# PCB_REVISION2WORKING.net
KiCad netlist of a schematic drawn in EAGLE
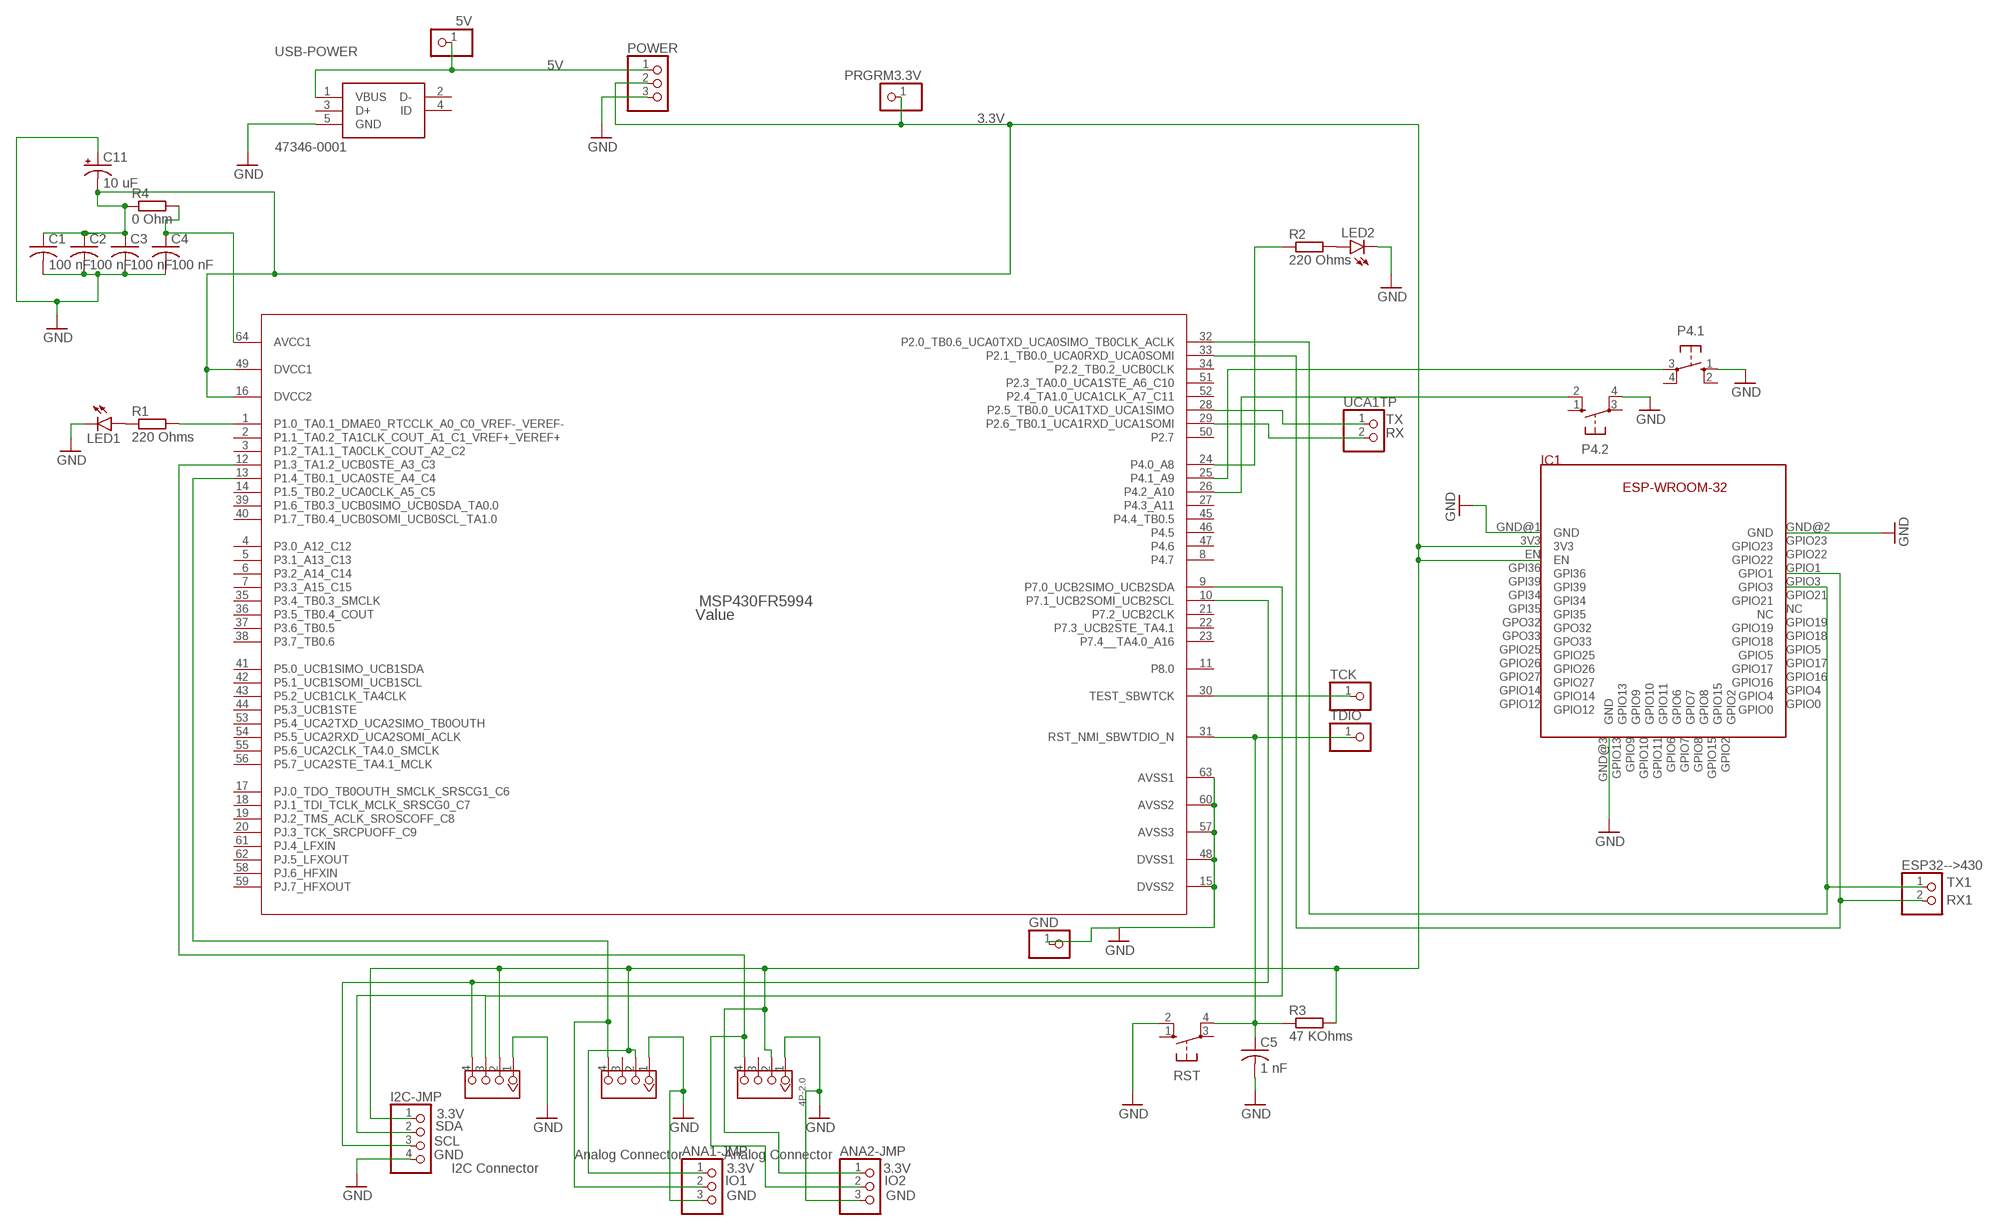
[diagram p0: schematic, sheet 1]

(export (version "E")
  (design (tool "Eeschema 10.0.6"))
  (components
    (comp (ref "5V")
      (value "PINHD-1X1")
      (footprint "eagle-import:1X01")
      (libsource (lib "eagle-import") (part "PINHD-1X1"))
    )
    (comp (ref "ANA1-JMP")
      (value "PINHD-1X3")
      (footprint "eagle-import:1X03")
      (libsource (lib "eagle-import") (part "PINHD-1X3"))
    )
    (comp (ref "ANA2-JMP")
      (value "PINHD-1X3")
      (footprint "eagle-import:1X03")
      (libsource (lib "eagle-import") (part "PINHD-1X3"))
    )
    (comp (ref "ANALOG1")
      (value "4P-2.0")
      (footprint "eagle-import:HW4-2.0")
      (libsource (lib "eagle-import") (part "GROVE-CONNECTOR-DIP(4P-2.0)"))
    )
    (comp (ref "ANALOG2")
      (value "4P-2.0")
      (footprint "eagle-import:HW4-2.0")
      (libsource (lib "eagle-import") (part "GROVE-CONNECTOR-DIP(4P-2.0)"))
    )
    (comp (ref "C1")
      (value "100 nF")
      (footprint "eagle-import:C0805K")
      (libsource (lib "eagle-import") (part "C-USC0805K"))
    )
    (comp (ref "C2")
      (value "100 nF")
      (footprint "eagle-import:C0805K")
      (libsource (lib "eagle-import") (part "C-USC0805K"))
    )
    (comp (ref "C3")
      (value "100 nF")
      (footprint "eagle-import:C0805K")
      (libsource (lib "eagle-import") (part "C-USC0805K"))
    )
    (comp (ref "C4")
      (value "100 nF")
      (footprint "eagle-import:C0805K")
      (libsource (lib "eagle-import") (part "C-USC0805K"))
    )
    (comp (ref "C5")
      (value "1 nF")
      (footprint "eagle-import:C0805K")
      (libsource (lib "eagle-import") (part "C-USC0805K"))
    )
    (comp (ref "C11")
      (value "10 uF")
      (footprint "eagle-import:E5-6")
      (libsource (lib "eagle-import") (part "CPOL-USE5-6"))
    )
    (comp (ref "ESP32-->430")
      (value "PINHD-1X2")
      (footprint "eagle-import:1X02")
      (libsource (lib "eagle-import") (part "PINHD-1X2"))
    )
    (comp (ref "GND")
      (value "PINHD-1X1")
      (footprint "eagle-import:1X01")
      (libsource (lib "eagle-import") (part "PINHD-1X1"))
    )
    (comp (ref "I2C")
      (value "4P-2.0")
      (footprint "eagle-import:HW4-2.0")
      (libsource (lib "eagle-import") (part "GROVE-CONNECTOR-DIP(4P-2.0)"))
    )
    (comp (ref "I2C-JMP")
      (value "PINHD-1X4")
      (footprint "eagle-import:1X04")
      (libsource (lib "eagle-import") (part "PINHD-1X4"))
    )
    (comp (ref "IC1")
      (value "ESPWROOM32")
      (footprint "eagle-import:ESPWROOM32")
      (libsource (lib "eagle-import") (part "ESPWROOM32"))
    )
    (comp (ref "LED1")
      (value "LED5MM")
      (footprint "eagle-import:LED5MM")
      (libsource (lib "eagle-import") (part "LED5MM"))
    )
    (comp (ref "LED2")
      (value "LED5MM")
      (footprint "eagle-import:LED5MM")
      (libsource (lib "eagle-import") (part "LED5MM"))
    )
    (comp (ref "MSP430FR5994")
      (value "Value")
      (footprint "eagle-import:PM0064A_N")
      (fields
        (field (name "MANUFACTURER") "Texas Instruments")
        (field (name "PARTNUMBER") "MSP430FR5964IPMR")
      )
      (libsource (lib "eagle-import") (part "MSP430FR5964IPMR"))
    )
    (comp (ref "P4.1")
      (value "10-XX")
      (footprint "eagle-import:B3F-10XX")
      (fields (field (name "MPN") "B3F-1000"))
      (libsource (lib "eagle-import") (part "10-XX"))
    )
    (comp (ref "P4.2")
      (value "10-XX")
      (footprint "eagle-import:B3F-10XX")
      (fields (field (name "MPN") "B3F-1000"))
      (libsource (lib "eagle-import") (part "10-XX"))
    )
    (comp (ref "POWER")
      (value "PINHD-1X3")
      (footprint "eagle-import:1X03")
      (libsource (lib "eagle-import") (part "PINHD-1X3"))
    )
    (comp (ref "PRGRM3.3V")
      (value "PINHD-1X1")
      (footprint "eagle-import:1X01")
      (libsource (lib "eagle-import") (part "PINHD-1X1"))
    )
    (comp (ref "R1")
      (value "220 Ohms")
      (footprint "eagle-import:M1206")
      (libsource (lib "eagle-import") (part "R-EU_M1206"))
    )
    (comp (ref "R2")
      (value "220 Ohms")
      (footprint "eagle-import:M1206")
      (libsource (lib "eagle-import") (part "R-EU_M1206"))
    )
    (comp (ref "R3")
      (value "47 KOhms")
      (footprint "eagle-import:M1206")
      (libsource (lib "eagle-import") (part "R-EU_M1206"))
    )
    (comp (ref "R4")
      (value "0 Ohm")
      (footprint "eagle-import:M1206")
      (libsource (lib "eagle-import") (part "R-EU_M1206"))
    )
    (comp (ref "RST")
      (value "10-XX")
      (footprint "eagle-import:B3F-10XX")
      (fields (field (name "MPN") "B3F-1000"))
      (libsource (lib "eagle-import") (part "10-XX"))
    )
    (comp (ref "TCK")
      (value "PINHD-1X1")
      (footprint "eagle-import:1X01")
      (libsource (lib "eagle-import") (part "PINHD-1X1"))
    )
    (comp (ref "TDIO")
      (value "PINHD-1X1")
      (footprint "eagle-import:1X01")
      (libsource (lib "eagle-import") (part "PINHD-1X1"))
    )
    (comp (ref "UCA1TP")
      (value "PINHD-1X2")
      (footprint "eagle-import:1X02")
      (libsource (lib "eagle-import") (part "PINHD-1X2"))
    )
    (comp (ref "USB-POWER")
      (value "47346-0001")
      (footprint "eagle-import:47346-0001")
      (fields (field (name "MOUSER_PART_NUMBER") "538-47346-0001"))
      (libsource (lib "eagle-import") (part "47346-0001"))
    )
  )
  (nets
    (net (code "1") (name "/3.3V") (class "Default")
      (node (ref "ANA1-JMP") (pin "1") (pinfunction "1_1") (pintype "passive"))
      (node (ref "ANA2-JMP") (pin "1") (pinfunction "1_1") (pintype "passive"))
      (node (ref "ANALOG1") (pin "2") (pinfunction "2_2") (pintype "bidirectional"))
      (node (ref "ANALOG2") (pin "2") (pinfunction "2_2") (pintype "bidirectional"))
      (node (ref "C1") (pin "1") (pinfunction "1_1") (pintype "passive"))
      (node (ref "C11") (pin "-") (pinfunction "-_-") (pintype "passive"))
      (node (ref "C2") (pin "1") (pinfunction "1_1") (pintype "passive"))
      (node (ref "C3") (pin "1") (pinfunction "1_1") (pintype "passive"))
      (node (ref "I2C") (pin "2") (pinfunction "2_2") (pintype "bidirectional"))
      (node (ref "I2C-JMP") (pin "1") (pinfunction "1_1") (pintype "passive"))
      (node (ref "IC1") (pin "3V3") (pinfunction "3V3_3V3") (pintype "bidirectional"))
      (node (ref "IC1") (pin "EN") (pinfunction "EN_EN") (pintype "bidirectional"))
      (node (ref "MSP430FR5994") (pin "16") (pinfunction "DVCC2_16") (pintype "power_in"))
      (node (ref "MSP430FR5994") (pin "49") (pinfunction "DVCC1_49") (pintype "power_in"))
      (node (ref "POWER") (pin "2") (pinfunction "2_2") (pintype "passive"))
      (node (ref "PRGRM3.3V") (pin "1") (pinfunction "1_1") (pintype "passive"))
      (node (ref "R3") (pin "2") (pinfunction "2_2") (pintype "passive"))
      (node (ref "R4") (pin "1") (pinfunction "1_1") (pintype "passive"))
    )
    (net (code "2") (name "/5V") (class "Default")
      (node (ref "5V") (pin "1") (pinfunction "1_1") (pintype "passive"))
      (node (ref "POWER") (pin "1") (pinfunction "1_1") (pintype "passive"))
      (node (ref "USB-POWER") (pin "1") (pinfunction "VBUS_1") (pintype "bidirectional"))
    )
    (net (code "3") (name "/IO1") (class "Default")
      (node (ref "ANA1-JMP") (pin "2") (pinfunction "2_2") (pintype "passive"))
      (node (ref "ANALOG1") (pin "4") (pinfunction "4_4") (pintype "bidirectional"))
      (node (ref "MSP430FR5994") (pin "13") (pinfunction "P1.4_TB0.1_UCA0STE_A4_C4_13") (pintype "bidirectional"))
    )
    (net (code "4") (name "/IO2") (class "Default")
      (node (ref "ANA2-JMP") (pin "2") (pinfunction "2_2") (pintype "passive"))
      (node (ref "ANALOG2") (pin "4") (pinfunction "4_4") (pintype "bidirectional"))
      (node (ref "MSP430FR5994") (pin "12") (pinfunction "P1.3_TA1.2_UCB0STE_A3_C3_12") (pintype "bidirectional"))
    )
    (net (code "5") (name "/RX") (class "Default")
      (node (ref "MSP430FR5994") (pin "29") (pinfunction "P2.6_TB0.1_UCA1RXD_UCA1SOMI_29") (pintype "bidirectional"))
      (node (ref "UCA1TP") (pin "2") (pinfunction "2_2") (pintype "passive"))
    )
    (net (code "6") (name "/RX1") (class "Default")
      (node (ref "ESP32-->430") (pin "2") (pinfunction "2_2") (pintype "passive"))
      (node (ref "IC1") (pin "GPIO1") (pinfunction "GPIO1_GPIO1") (pintype "bidirectional"))
      (node (ref "MSP430FR5994") (pin "33") (pinfunction "P2.1_TB0.0_UCA0RXD_UCA0SOMI_33") (pintype "bidirectional"))
    )
    (net (code "7") (name "/SCL") (class "Default")
      (node (ref "I2C") (pin "4") (pinfunction "4_4") (pintype "bidirectional"))
      (node (ref "I2C-JMP") (pin "3") (pinfunction "3_3") (pintype "passive"))
      (node (ref "MSP430FR5994") (pin "10") (pinfunction "P7.1_UCB2SOMI_UCB2SCL_10") (pintype "bidirectional"))
    )
    (net (code "8") (name "/SDA") (class "Default")
      (node (ref "I2C") (pin "3") (pinfunction "3_3") (pintype "bidirectional"))
      (node (ref "I2C-JMP") (pin "2") (pinfunction "2_2") (pintype "passive"))
      (node (ref "MSP430FR5994") (pin "9") (pinfunction "P7.0_UCB2SIMO_UCB2SDA_9") (pintype "bidirectional"))
    )
    (net (code "9") (name "/TX") (class "Default")
      (node (ref "MSP430FR5994") (pin "28") (pinfunction "P2.5_TB0.0_UCA1TXD_UCA1SIMO_28") (pintype "bidirectional"))
      (node (ref "UCA1TP") (pin "1") (pinfunction "1_1") (pintype "passive"))
    )
    (net (code "10") (name "/TX1") (class "Default")
      (node (ref "ESP32-->430") (pin "1") (pinfunction "1_1") (pintype "passive"))
      (node (ref "IC1") (pin "GPIO3") (pinfunction "GPIO3_GPIO3") (pintype "bidirectional"))
      (node (ref "MSP430FR5994") (pin "32") (pinfunction "P2.0_TB0.6_UCA0TXD_UCA0SIMO_TB0CLK_ACLK_32") (pintype "bidirectional"))
    )
    (net (code "11") (name "GND") (class "Default")
      (node (ref "ANA1-JMP") (pin "3") (pinfunction "3_3") (pintype "passive"))
      (node (ref "ANA2-JMP") (pin "3") (pinfunction "3_3") (pintype "passive"))
      (node (ref "ANALOG1") (pin "1") (pinfunction "1_1") (pintype "bidirectional"))
      (node (ref "ANALOG2") (pin "1") (pinfunction "1_1") (pintype "bidirectional"))
      (node (ref "C1") (pin "2") (pinfunction "2_2") (pintype "passive"))
      (node (ref "C11") (pin "+") (pinfunction "+_+") (pintype "passive"))
      (node (ref "C2") (pin "2") (pinfunction "2_2") (pintype "passive"))
      (node (ref "C3") (pin "2") (pinfunction "2_2") (pintype "passive"))
      (node (ref "C4") (pin "2") (pinfunction "2_2") (pintype "passive"))
      (node (ref "C5") (pin "2") (pinfunction "2_2") (pintype "passive"))
      (node (ref "GND") (pin "1") (pinfunction "1_1") (pintype "passive"))
      (node (ref "I2C") (pin "1") (pinfunction "1_1") (pintype "bidirectional"))
      (node (ref "I2C-JMP") (pin "4") (pinfunction "4_4") (pintype "passive"))
      (node (ref "IC1") (pin "GND@1") (pinfunction "GND_GND@1") (pintype "bidirectional"))
      (node (ref "IC1") (pin "GND@2") (pinfunction "GND_GND@2") (pintype "bidirectional"))
      (node (ref "IC1") (pin "GND@3") (pinfunction "GND_GND@3") (pintype "bidirectional"))
      (node (ref "LED1") (pin "K") (pinfunction "C_K") (pintype "passive"))
      (node (ref "LED2") (pin "K") (pinfunction "C_K") (pintype "passive"))
      (node (ref "MSP430FR5994") (pin "15") (pinfunction "DVSS2_15") (pintype "power_in"))
      (node (ref "MSP430FR5994") (pin "48") (pinfunction "DVSS1_48") (pintype "power_in"))
      (node (ref "MSP430FR5994") (pin "57") (pinfunction "AVSS3_57") (pintype "power_in"))
      (node (ref "MSP430FR5994") (pin "60") (pinfunction "AVSS2_60") (pintype "power_in"))
      (node (ref "MSP430FR5994") (pin "63") (pinfunction "AVSS1_63") (pintype "power_in"))
      (node (ref "P4.1") (pin "1") (pinfunction "S_1") (pintype "passive"))
      (node (ref "P4.2") (pin "4") (pinfunction "P1_4") (pintype "passive"))
      (node (ref "POWER") (pin "3") (pinfunction "3_3") (pintype "passive"))
      (node (ref "RST") (pin "2") (pinfunction "S1_2") (pintype "passive"))
      (node (ref "USB-POWER") (pin "5") (pinfunction "GND_5") (pintype "bidirectional"))
    )
    (net (code "12") (name "Net-(LED1-PadA)") (class "Default")
      (node (ref "LED1") (pin "A") (pinfunction "A_A") (pintype "passive"))
      (node (ref "R1") (pin "1") (pinfunction "1_1") (pintype "passive"))
    )
    (net (code "13") (name "Net-(LED2-PadA)") (class "Default")
      (node (ref "LED2") (pin "A") (pinfunction "A_A") (pintype "passive"))
      (node (ref "R2") (pin "2") (pinfunction "2_2") (pintype "passive"))
    )
    (net (code "14") (name "Net-(MSP430FR5994-AVCC1)") (class "Default")
      (node (ref "C4") (pin "1") (pinfunction "1_1") (pintype "passive"))
      (node (ref "MSP430FR5994") (pin "64") (pinfunction "AVCC1_64") (pintype "power_in"))
      (node (ref "R4") (pin "2") (pinfunction "2_2") (pintype "passive"))
    )
    (net (code "15") (name "Net-(MSP430FR5994-P1.0_TA0.1_DMAE0_RTCCLK_A0_C0_VREF-_VEREF-)") (class "Default")
      (node (ref "MSP430FR5994") (pin "1") (pinfunction "P1.0_TA0.1_DMAE0_RTCCLK_A0_C0_VREF-_VEREF-_1") (pintype "bidirectional"))
      (node (ref "R1") (pin "2") (pinfunction "2_2") (pintype "passive"))
    )
    (net (code "16") (name "Net-(MSP430FR5994-P4.0_A8)") (class "Default")
      (node (ref "MSP430FR5994") (pin "24") (pinfunction "P4.0_A8_24") (pintype "bidirectional"))
      (node (ref "R2") (pin "1") (pinfunction "1_1") (pintype "passive"))
    )
    (net (code "17") (name "Net-(MSP430FR5994-P4.1_A9)") (class "Default")
      (node (ref "MSP430FR5994") (pin "25") (pinfunction "P4.1_A9_25") (pintype "bidirectional"))
      (node (ref "P4.1") (pin "3") (pinfunction "P_3") (pintype "passive"))
    )
    (net (code "18") (name "Net-(MSP430FR5994-P4.2_A10)") (class "Default")
      (node (ref "MSP430FR5994") (pin "26") (pinfunction "P4.2_A10_26") (pintype "bidirectional"))
      (node (ref "P4.2") (pin "2") (pinfunction "S1_2") (pintype "passive"))
    )
    (net (code "19") (name "Net-(MSP430FR5994-RST_NMI_SBWTDIO_N)") (class "Default")
      (node (ref "C5") (pin "1") (pinfunction "1_1") (pintype "passive"))
      (node (ref "MSP430FR5994") (pin "31") (pinfunction "RST_NMI_SBWTDIO_N_31") (pintype "bidirectional"))
      (node (ref "R3") (pin "1") (pinfunction "1_1") (pintype "passive"))
      (node (ref "RST") (pin "4") (pinfunction "P1_4") (pintype "passive"))
      (node (ref "TDIO") (pin "1") (pinfunction "1_1") (pintype "passive"))
    )
    (net (code "20") (name "Net-(MSP430FR5994-TEST_SBWTCK)") (class "Default")
      (node (ref "MSP430FR5994") (pin "30") (pinfunction "TEST_SBWTCK_30") (pintype "input"))
      (node (ref "TCK") (pin "1") (pinfunction "1_1") (pintype "passive"))
    )
    (net (code "21") (name "unconnected-(ANALOG1-Pad3)") (class "Default")
      (node (ref "ANALOG1") (pin "3") (pinfunction "3_3") (pintype "bidirectional"))
    )
    (net (code "22") (name "unconnected-(ANALOG2-Pad3)") (class "Default")
      (node (ref "ANALOG2") (pin "3") (pinfunction "3_3") (pintype "bidirectional"))
    )
    (net (code "23") (name "unconnected-(IC1-PadGPI34)") (class "Default")
      (node (ref "IC1") (pin "GPI34") (pinfunction "GPI34_GPI34") (pintype "bidirectional"))
    )
    (net (code "24") (name "unconnected-(IC1-PadGPI35)") (class "Default")
      (node (ref "IC1") (pin "GPI35") (pinfunction "GPI35_GPI35") (pintype "bidirectional"))
    )
    (net (code "25") (name "unconnected-(IC1-PadGPI36)") (class "Default")
      (node (ref "IC1") (pin "GPI36") (pinfunction "GPI36_GPI36") (pintype "bidirectional"))
    )
    (net (code "26") (name "unconnected-(IC1-PadGPI39)") (class "Default")
      (node (ref "IC1") (pin "GPI39") (pinfunction "GPI39_GPI39") (pintype "bidirectional"))
    )
    (net (code "27") (name "unconnected-(IC1-PadGPIO0)") (class "Default")
      (node (ref "IC1") (pin "GPIO0") (pinfunction "GPIO0_GPIO0") (pintype "bidirectional"))
    )
    (net (code "28") (name "unconnected-(IC1-PadGPIO2)") (class "Default")
      (node (ref "IC1") (pin "GPIO2") (pinfunction "GPIO2_GPIO2") (pintype "bidirectional"))
    )
    (net (code "29") (name "unconnected-(IC1-PadGPIO4)") (class "Default")
      (node (ref "IC1") (pin "GPIO4") (pinfunction "GPIO4_GPIO4") (pintype "bidirectional"))
    )
    (net (code "30") (name "unconnected-(IC1-PadGPIO5)") (class "Default")
      (node (ref "IC1") (pin "GPIO5") (pinfunction "GPIO5_GPIO5") (pintype "bidirectional"))
    )
    (net (code "31") (name "unconnected-(IC1-PadGPIO6)") (class "Default")
      (node (ref "IC1") (pin "GPIO6") (pinfunction "GPIO6_GPIO6") (pintype "bidirectional"))
    )
    (net (code "32") (name "unconnected-(IC1-PadGPIO7)") (class "Default")
      (node (ref "IC1") (pin "GPIO7") (pinfunction "GPIO7_GPIO7") (pintype "bidirectional"))
    )
    (net (code "33") (name "unconnected-(IC1-PadGPIO8)") (class "Default")
      (node (ref "IC1") (pin "GPIO8") (pinfunction "GPIO8_GPIO8") (pintype "bidirectional"))
    )
    (net (code "34") (name "unconnected-(IC1-PadGPIO9)") (class "Default")
      (node (ref "IC1") (pin "GPIO9") (pinfunction "GPIO9_GPIO9") (pintype "bidirectional"))
    )
    (net (code "35") (name "unconnected-(IC1-PadGPIO10)") (class "Default")
      (node (ref "IC1") (pin "GPIO10") (pinfunction "GPIO10_GPIO10") (pintype "bidirectional"))
    )
    (net (code "36") (name "unconnected-(IC1-PadGPIO11)") (class "Default")
      (node (ref "IC1") (pin "GPIO11") (pinfunction "GPIO11_GPIO11") (pintype "bidirectional"))
    )
    (net (code "37") (name "unconnected-(IC1-PadGPIO12)") (class "Default")
      (node (ref "IC1") (pin "GPIO12") (pinfunction "GPIO12_GPIO12") (pintype "bidirectional"))
    )
    (net (code "38") (name "unconnected-(IC1-PadGPIO13)") (class "Default")
      (node (ref "IC1") (pin "GPIO13") (pinfunction "GPIO13_GPIO13") (pintype "bidirectional"))
    )
    (net (code "39") (name "unconnected-(IC1-PadGPIO14)") (class "Default")
      (node (ref "IC1") (pin "GPIO14") (pinfunction "GPIO14_GPIO14") (pintype "bidirectional"))
    )
    (net (code "40") (name "unconnected-(IC1-PadGPIO15)") (class "Default")
      (node (ref "IC1") (pin "GPIO15") (pinfunction "GPIO15_GPIO15") (pintype "bidirectional"))
    )
    (net (code "41") (name "unconnected-(IC1-PadGPIO16)") (class "Default")
      (node (ref "IC1") (pin "GPIO16") (pinfunction "GPIO16_GPIO16") (pintype "bidirectional"))
    )
    (net (code "42") (name "unconnected-(IC1-PadGPIO17)") (class "Default")
      (node (ref "IC1") (pin "GPIO17") (pinfunction "GPIO17_GPIO17") (pintype "bidirectional"))
    )
    (net (code "43") (name "unconnected-(IC1-PadGPIO18)") (class "Default")
      (node (ref "IC1") (pin "GPIO18") (pinfunction "GPIO18_GPIO18") (pintype "bidirectional"))
    )
    (net (code "44") (name "unconnected-(IC1-PadGPIO19)") (class "Default")
      (node (ref "IC1") (pin "GPIO19") (pinfunction "GPIO19_GPIO19") (pintype "bidirectional"))
    )
    (net (code "45") (name "unconnected-(IC1-PadGPIO21)") (class "Default")
      (node (ref "IC1") (pin "GPIO21") (pinfunction "GPIO21_GPIO21") (pintype "bidirectional"))
    )
    (net (code "46") (name "unconnected-(IC1-PadGPIO22)") (class "Default")
      (node (ref "IC1") (pin "GPIO22") (pinfunction "GPIO22_GPIO22") (pintype "bidirectional"))
    )
    (net (code "47") (name "unconnected-(IC1-PadGPIO23)") (class "Default")
      (node (ref "IC1") (pin "GPIO23") (pinfunction "GPIO23_GPIO23") (pintype "bidirectional"))
    )
    (net (code "48") (name "unconnected-(IC1-PadGPIO25)") (class "Default")
      (node (ref "IC1") (pin "GPIO25") (pinfunction "GPIO25_GPIO25") (pintype "bidirectional"))
    )
    (net (code "49") (name "unconnected-(IC1-PadGPIO26)") (class "Default")
      (node (ref "IC1") (pin "GPIO26") (pinfunction "GPIO26_GPIO26") (pintype "bidirectional"))
    )
    (net (code "50") (name "unconnected-(IC1-PadGPIO27)") (class "Default")
      (node (ref "IC1") (pin "GPIO27") (pinfunction "GPIO27_GPIO27") (pintype "bidirectional"))
    )
    (net (code "51") (name "unconnected-(IC1-PadGPO32)") (class "Default")
      (node (ref "IC1") (pin "GPO32") (pinfunction "GPO32_GPO32") (pintype "bidirectional"))
    )
    (net (code "52") (name "unconnected-(IC1-PadGPO33)") (class "Default")
      (node (ref "IC1") (pin "GPO33") (pinfunction "GPO33_GPO33") (pintype "bidirectional"))
    )
    (net (code "53") (name "unconnected-(IC1-PadNC)") (class "Default")
      (node (ref "IC1") (pin "NC") (pinfunction "NC_NC") (pintype "bidirectional"))
    )
    (net (code "54") (name "unconnected-(MSP430FR5994-P1.1_TA0.2_TA1CLK_COUT_A1_C1_VREF+_VEREF+-Pad2)") (class "Default")
      (node (ref "MSP430FR5994") (pin "2") (pinfunction "P1.1_TA0.2_TA1CLK_COUT_A1_C1_VREF+_VEREF+_2") (pintype "bidirectional"))
    )
    (net (code "55") (name "unconnected-(MSP430FR5994-P1.2_TA1.1_TA0CLK_COUT_A2_C2-Pad3)") (class "Default")
      (node (ref "MSP430FR5994") (pin "3") (pinfunction "P1.2_TA1.1_TA0CLK_COUT_A2_C2_3") (pintype "bidirectional"))
    )
    (net (code "56") (name "unconnected-(MSP430FR5994-P1.5_TB0.2_UCA0CLK_A5_C5-Pad14)") (class "Default")
      (node (ref "MSP430FR5994") (pin "14") (pinfunction "P1.5_TB0.2_UCA0CLK_A5_C5_14") (pintype "bidirectional"))
    )
    (net (code "57") (name "unconnected-(MSP430FR5994-P1.6_TB0.3_UCB0SIMO_UCB0SDA_TA0.0-Pad39)") (class "Default")
      (node (ref "MSP430FR5994") (pin "39") (pinfunction "P1.6_TB0.3_UCB0SIMO_UCB0SDA_TA0.0_39") (pintype "bidirectional"))
    )
    (net (code "58") (name "unconnected-(MSP430FR5994-P1.7_TB0.4_UCB0SOMI_UCB0SCL_TA1.0-Pad40)") (class "Default")
      (node (ref "MSP430FR5994") (pin "40") (pinfunction "P1.7_TB0.4_UCB0SOMI_UCB0SCL_TA1.0_40") (pintype "bidirectional"))
    )
    (net (code "59") (name "unconnected-(MSP430FR5994-P2.2_TB0.2_UCB0CLK-Pad34)") (class "Default")
      (node (ref "MSP430FR5994") (pin "34") (pinfunction "P2.2_TB0.2_UCB0CLK_34") (pintype "bidirectional"))
    )
    (net (code "60") (name "unconnected-(MSP430FR5994-P2.3_TA0.0_UCA1STE_A6_C10-Pad51)") (class "Default")
      (node (ref "MSP430FR5994") (pin "51") (pinfunction "P2.3_TA0.0_UCA1STE_A6_C10_51") (pintype "bidirectional"))
    )
    (net (code "61") (name "unconnected-(MSP430FR5994-P2.4_TA1.0_UCA1CLK_A7_C11-Pad52)") (class "Default")
      (node (ref "MSP430FR5994") (pin "52") (pinfunction "P2.4_TA1.0_UCA1CLK_A7_C11_52") (pintype "bidirectional"))
    )
    (net (code "62") (name "unconnected-(MSP430FR5994-P2.7-Pad50)") (class "Default")
      (node (ref "MSP430FR5994") (pin "50") (pinfunction "P2.7_50") (pintype "bidirectional"))
    )
    (net (code "63") (name "unconnected-(MSP430FR5994-P3.0_A12_C12-Pad4)") (class "Default")
      (node (ref "MSP430FR5994") (pin "4") (pinfunction "P3.0_A12_C12_4") (pintype "bidirectional"))
    )
    (net (code "64") (name "unconnected-(MSP430FR5994-P3.1_A13_C13-Pad5)") (class "Default")
      (node (ref "MSP430FR5994") (pin "5") (pinfunction "P3.1_A13_C13_5") (pintype "bidirectional"))
    )
    (net (code "65") (name "unconnected-(MSP430FR5994-P3.2_A14_C14-Pad6)") (class "Default")
      (node (ref "MSP430FR5994") (pin "6") (pinfunction "P3.2_A14_C14_6") (pintype "bidirectional"))
    )
    (net (code "66") (name "unconnected-(MSP430FR5994-P3.3_A15_C15-Pad7)") (class "Default")
      (node (ref "MSP430FR5994") (pin "7") (pinfunction "P3.3_A15_C15_7") (pintype "bidirectional"))
    )
    (net (code "67") (name "unconnected-(MSP430FR5994-P3.4_TB0.3_SMCLK-Pad35)") (class "Default")
      (node (ref "MSP430FR5994") (pin "35") (pinfunction "P3.4_TB0.3_SMCLK_35") (pintype "bidirectional"))
    )
    (net (code "68") (name "unconnected-(MSP430FR5994-P3.5_TB0.4_COUT-Pad36)") (class "Default")
      (node (ref "MSP430FR5994") (pin "36") (pinfunction "P3.5_TB0.4_COUT_36") (pintype "bidirectional"))
    )
    (net (code "69") (name "unconnected-(MSP430FR5994-P3.6_TB0.5-Pad37)") (class "Default")
      (node (ref "MSP430FR5994") (pin "37") (pinfunction "P3.6_TB0.5_37") (pintype "bidirectional"))
    )
    (net (code "70") (name "unconnected-(MSP430FR5994-P3.7_TB0.6-Pad38)") (class "Default")
      (node (ref "MSP430FR5994") (pin "38") (pinfunction "P3.7_TB0.6_38") (pintype "bidirectional"))
    )
    (net (code "71") (name "unconnected-(MSP430FR5994-P4.3_A11-Pad27)") (class "Default")
      (node (ref "MSP430FR5994") (pin "27") (pinfunction "P4.3_A11_27") (pintype "bidirectional"))
    )
    (net (code "72") (name "unconnected-(MSP430FR5994-P4.4_TB0.5-Pad45)") (class "Default")
      (node (ref "MSP430FR5994") (pin "45") (pinfunction "P4.4_TB0.5_45") (pintype "bidirectional"))
    )
    (net (code "73") (name "unconnected-(MSP430FR5994-P4.5-Pad46)") (class "Default")
      (node (ref "MSP430FR5994") (pin "46") (pinfunction "P4.5_46") (pintype "bidirectional"))
    )
    (net (code "74") (name "unconnected-(MSP430FR5994-P4.6-Pad47)") (class "Default")
      (node (ref "MSP430FR5994") (pin "47") (pinfunction "P4.6_47") (pintype "bidirectional"))
    )
    (net (code "75") (name "unconnected-(MSP430FR5994-P4.7-Pad8)") (class "Default")
      (node (ref "MSP430FR5994") (pin "8") (pinfunction "P4.7_8") (pintype "bidirectional"))
    )
    (net (code "76") (name "unconnected-(MSP430FR5994-P5.0_UCB1SIMO_UCB1SDA-Pad41)") (class "Default")
      (node (ref "MSP430FR5994") (pin "41") (pinfunction "P5.0_UCB1SIMO_UCB1SDA_41") (pintype "bidirectional"))
    )
    (net (code "77") (name "unconnected-(MSP430FR5994-P5.1_UCB1SOMI_UCB1SCL-Pad42)") (class "Default")
      (node (ref "MSP430FR5994") (pin "42") (pinfunction "P5.1_UCB1SOMI_UCB1SCL_42") (pintype "bidirectional"))
    )
    (net (code "78") (name "unconnected-(MSP430FR5994-P5.2_UCB1CLK_TA4CLK-Pad43)") (class "Default")
      (node (ref "MSP430FR5994") (pin "43") (pinfunction "P5.2_UCB1CLK_TA4CLK_43") (pintype "bidirectional"))
    )
    (net (code "79") (name "unconnected-(MSP430FR5994-P5.3_UCB1STE-Pad44)") (class "Default")
      (node (ref "MSP430FR5994") (pin "44") (pinfunction "P5.3_UCB1STE_44") (pintype "bidirectional"))
    )
    (net (code "80") (name "unconnected-(MSP430FR5994-P5.4_UCA2TXD_UCA2SIMO_TB0OUTH-Pad53)") (class "Default")
      (node (ref "MSP430FR5994") (pin "53") (pinfunction "P5.4_UCA2TXD_UCA2SIMO_TB0OUTH_53") (pintype "bidirectional"))
    )
    (net (code "81") (name "unconnected-(MSP430FR5994-P5.5_UCA2RXD_UCA2SOMI_ACLK-Pad54)") (class "Default")
      (node (ref "MSP430FR5994") (pin "54") (pinfunction "P5.5_UCA2RXD_UCA2SOMI_ACLK_54") (pintype "bidirectional"))
    )
    (net (code "82") (name "unconnected-(MSP430FR5994-P5.6_UCA2CLK_TA4.0_SMCLK-Pad55)") (class "Default")
      (node (ref "MSP430FR5994") (pin "55") (pinfunction "P5.6_UCA2CLK_TA4.0_SMCLK_55") (pintype "bidirectional"))
    )
    (net (code "83") (name "unconnected-(MSP430FR5994-P5.7_UCA2STE_TA4.1_MCLK-Pad56)") (class "Default")
      (node (ref "MSP430FR5994") (pin "56") (pinfunction "P5.7_UCA2STE_TA4.1_MCLK_56") (pintype "bidirectional"))
    )
    (net (code "84") (name "unconnected-(MSP430FR5994-P7.2_UCB2CLK-Pad21)") (class "Default")
      (node (ref "MSP430FR5994") (pin "21") (pinfunction "P7.2_UCB2CLK_21") (pintype "bidirectional"))
    )
    (net (code "85") (name "unconnected-(MSP430FR5994-P7.3_UCB2STE_TA4.1-Pad22)") (class "Default")
      (node (ref "MSP430FR5994") (pin "22") (pinfunction "P7.3_UCB2STE_TA4.1_22") (pintype "bidirectional"))
    )
    (net (code "86") (name "unconnected-(MSP430FR5994-P7.4__TA4.0_A16-Pad23)") (class "Default")
      (node (ref "MSP430FR5994") (pin "23") (pinfunction "P7.4__TA4.0_A16_23") (pintype "bidirectional"))
    )
    (net (code "87") (name "unconnected-(MSP430FR5994-P8.0-Pad11)") (class "Default")
      (node (ref "MSP430FR5994") (pin "11") (pinfunction "P8.0_11") (pintype "bidirectional"))
    )
    (net (code "88") (name "unconnected-(MSP430FR5994-PJ.0_TDO_TB0OUTH_SMCLK_SRSCG1_C6-Pad17)") (class "Default")
      (node (ref "MSP430FR5994") (pin "17") (pinfunction "PJ.0_TDO_TB0OUTH_SMCLK_SRSCG1_C6_17") (pintype "bidirectional"))
    )
    (net (code "89") (name "unconnected-(MSP430FR5994-PJ.1_TDI_TCLK_MCLK_SRSCG0_C7-Pad18)") (class "Default")
      (node (ref "MSP430FR5994") (pin "18") (pinfunction "PJ.1_TDI_TCLK_MCLK_SRSCG0_C7_18") (pintype "bidirectional"))
    )
    (net (code "90") (name "unconnected-(MSP430FR5994-PJ.2_TMS_ACLK_SROSCOFF_C8-Pad19)") (class "Default")
      (node (ref "MSP430FR5994") (pin "19") (pinfunction "PJ.2_TMS_ACLK_SROSCOFF_C8_19") (pintype "bidirectional"))
    )
    (net (code "91") (name "unconnected-(MSP430FR5994-PJ.3_TCK_SRCPUOFF_C9-Pad20)") (class "Default")
      (node (ref "MSP430FR5994") (pin "20") (pinfunction "PJ.3_TCK_SRCPUOFF_C9_20") (pintype "bidirectional"))
    )
    (net (code "92") (name "unconnected-(MSP430FR5994-PJ.4_LFXIN-Pad61)") (class "Default")
      (node (ref "MSP430FR5994") (pin "61") (pinfunction "PJ.4_LFXIN_61") (pintype "bidirectional"))
    )
    (net (code "93") (name "unconnected-(MSP430FR5994-PJ.5_LFXOUT-Pad62)") (class "Default")
      (node (ref "MSP430FR5994") (pin "62") (pinfunction "PJ.5_LFXOUT_62") (pintype "bidirectional"))
    )
    (net (code "94") (name "unconnected-(MSP430FR5994-PJ.6_HFXIN-Pad58)") (class "Default")
      (node (ref "MSP430FR5994") (pin "58") (pinfunction "PJ.6_HFXIN_58") (pintype "bidirectional"))
    )
    (net (code "95") (name "unconnected-(MSP430FR5994-PJ.7_HFXOUT-Pad59)") (class "Default")
      (node (ref "MSP430FR5994") (pin "59") (pinfunction "PJ.7_HFXOUT_59") (pintype "bidirectional"))
    )
    (net (code "96") (name "unconnected-(P4.1-P1-Pad4)") (class "Default")
      (node (ref "P4.1") (pin "4") (pinfunction "P1_4") (pintype "passive"))
    )
    (net (code "97") (name "unconnected-(P4.1-S1-Pad2)") (class "Default")
      (node (ref "P4.1") (pin "2") (pinfunction "S1_2") (pintype "passive"))
    )
    (net (code "98") (name "unconnected-(P4.2-P-Pad3)") (class "Default")
      (node (ref "P4.2") (pin "3") (pinfunction "P_3") (pintype "passive"))
    )
    (net (code "99") (name "unconnected-(P4.2-S-Pad1)") (class "Default")
      (node (ref "P4.2") (pin "1") (pinfunction "S_1") (pintype "passive"))
    )
    (net (code "100") (name "unconnected-(RST-P-Pad3)") (class "Default")
      (node (ref "RST") (pin "3") (pinfunction "P_3") (pintype "passive"))
    )
    (net (code "101") (name "unconnected-(RST-S-Pad1)") (class "Default")
      (node (ref "RST") (pin "1") (pinfunction "S_1") (pintype "passive"))
    )
    (net (code "102") (name "unconnected-(USB-POWER-D+-Pad3)") (class "Default")
      (node (ref "USB-POWER") (pin "3") (pinfunction "D+_3") (pintype "bidirectional"))
    )
    (net (code "103") (name "unconnected-(USB-POWER-D--Pad2)") (class "Default")
      (node (ref "USB-POWER") (pin "2") (pinfunction "D-_2") (pintype "bidirectional"))
    )
    (net (code "104") (name "unconnected-(USB-POWER-ID-Pad4)") (class "Default")
      (node (ref "USB-POWER") (pin "4") (pinfunction "ID_4") (pintype "bidirectional"))
    )
  )
)
